# ESP32.net
KiCad netlist of a schematic drawn in Altium Designer
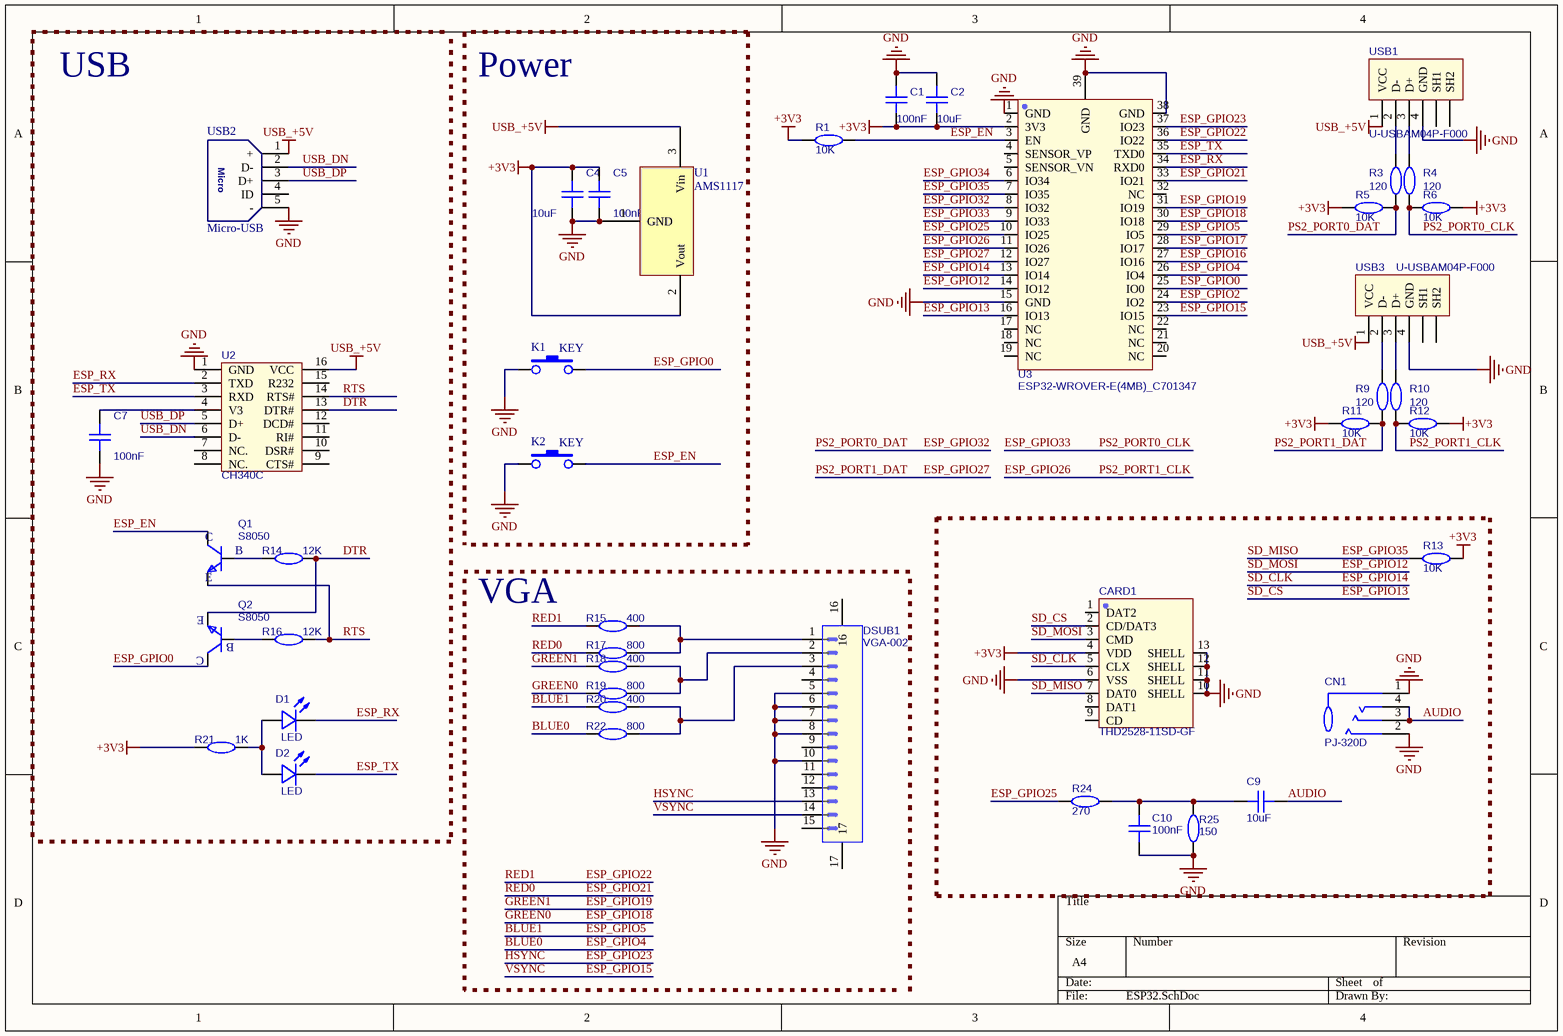
[diagram p0: ESP32.SchDoc]

(export (version "E")
  (design (tool "Eeschema 10.0.6"))
  (components
    (comp (ref "C1")
      (value "100nF")
      (footprint "0805C")
      (fields
        (field (name "BOM_SUPPLIER PART") "C325469")
        (field (name "BOM_MANUFACTURER PART") "CC0603GRNPO9BN200")
        (field (name "CONTRIBUTOR") "LCSC")
      )
      (libsource (lib "miscpcb") (part "CAP_0603"))
    )
    (comp (ref "C2")
      (value "10uF")
      (footprint "0805C")
      (fields
        (field (name "BOM_SUPPLIER PART") "C325469")
        (field (name "BOM_MANUFACTURER PART") "CC0603GRNPO9BN200")
        (field (name "CONTRIBUTOR") "LCSC")
      )
      (libsource (lib "miscpcb") (part "CAP_0603"))
    )
    (comp (ref "C4")
      (value "10uF")
      (footprint "0805C")
      (fields
        (field (name "BOM_SUPPLIER PART") "C325469")
        (field (name "BOM_MANUFACTURER PART") "CC0603GRNPO9BN200")
        (field (name "CONTRIBUTOR") "LCSC")
      )
      (libsource (lib "miscpcb") (part "CAP_0603"))
    )
    (comp (ref "C5")
      (value "100nF")
      (footprint "0805C")
      (fields
        (field (name "BOM_SUPPLIER PART") "C325469")
        (field (name "BOM_MANUFACTURER PART") "CC0603GRNPO9BN200")
        (field (name "CONTRIBUTOR") "LCSC")
      )
      (libsource (lib "miscpcb") (part "CAP_0603"))
    )
    (comp (ref "C7")
      (value "100nF")
      (footprint "0805C")
      (fields
        (field (name "BOM_SUPPLIER PART") "C325469")
        (field (name "BOM_MANUFACTURER PART") "CC0603GRNPO9BN200")
        (field (name "CONTRIBUTOR") "LCSC")
      )
      (libsource (lib "miscpcb") (part "CAP_0603"))
    )
    (comp (ref "C9")
      (value "10uF")
      (footprint "0805C")
      (fields
        (field (name "BOM_SUPPLIER PART") "C325469")
        (field (name "BOM_MANUFACTURER PART") "CC0603GRNPO9BN200")
        (field (name "CONTRIBUTOR") "LCSC")
      )
      (libsource (lib "miscpcb") (part "CAP_0603"))
    )
    (comp (ref "C10")
      (value "100nF")
      (footprint "0805C")
      (fields
        (field (name "BOM_SUPPLIER PART") "C325469")
        (field (name "BOM_MANUFACTURER PART") "CC0603GRNPO9BN200")
        (field (name "CONTRIBUTOR") "LCSC")
      )
      (libsource (lib "miscpcb") (part "CAP_0603"))
    )
    (comp (ref "CARD1")
      (value "THD2528-11SD-GF")
      (footprint "Micro SD")
      (fields (field (name "BOM_SUPPLIER PART") "C283232") (field (name "CONTRIBUTOR") "LCSC"))
      (libsource (lib "esp32") (part "THD2528-11SD-GF"))
    )
    (comp (ref "CN1")
      (value "PJ-320D")
      (footprint "AUDIO-SMD_PJ-320D")
      (fields (field (name "BOM_SUPPLIER PART") "C431535") (field (name "CONTRIBUTOR") "LCSC"))
      (libsource (lib "esp32") (part "PJ-320D"))
    )
    (comp (ref "D1")
      (value "LED")
      (footprint "LED-0603")
      (fields (field (name "BOM_MANUFACTURER PART") "?"))
      (libsource (lib "miscpcb") (part "LED-Y"))
    )
    (comp (ref "D2")
      (value "LED")
      (footprint "LED-0603")
      (fields (field (name "BOM_MANUFACTURER PART") "?"))
      (libsource (lib "miscpcb") (part "LED-Y"))
    )
    (comp (ref "DSUB1")
      (value "VGA-002")
      (footprint "VGA15/F/90")
      (fields (field (name "BOM_SUPPLIER PART") "C138387"))
      (libsource (lib "esp32") (part "VGA-002"))
    )
    (comp (ref "K1")
      (value "KEY")
      (footprint "SW-SMD_L3.9-W2.9-P4.15-LS5.0")
      (libsource (lib "开关-轻触开关") (part "KEY"))
    )
    (comp (ref "K2")
      (value "KEY")
      (footprint "SW-SMD_L3.9-W2.9-P4.15-LS5.0")
      (libsource (lib "开关-轻触开关") (part "KEY"))
    )
    (comp (ref "Q1")
      (value "S8050")
      (footprint "SOT-23_L2.9-W1.3-P0.95-LS2.4-BR")
      (fields (field (name "BOM_SUPPLIER PART") "C414195") (field (name "CONTRIBUTOR") "LCSC"))
      (libsource (lib "miscpcb") (part "S8050"))
    )
    (comp (ref "Q2")
      (value "S8050")
      (footprint "SOT-23_L2.9-W1.3-P0.95-LS2.4-BR")
      (fields (field (name "BOM_SUPPLIER PART") "C414195") (field (name "CONTRIBUTOR") "LCSC"))
      (libsource (lib "miscpcb") (part "S8050"))
    )
    (comp (ref "R1")
      (value "10K")
      (footprint "0805R")
      (fields
        (field (name "BOM_MANUFACTURER PART") "CR0603JA0301G")
        (field (name "BOM_SUPPLIER PART") "C101323")
      )
      (libsource (lib "miscpcb") (part "RES_0603"))
    )
    (comp (ref "R3")
      (value "120")
      (footprint "0805R")
      (fields
        (field (name "BOM_MANUFACTURER PART") "CR0603JA0301G")
        (field (name "BOM_SUPPLIER PART") "C101323")
      )
      (libsource (lib "miscpcb") (part "RES_0603"))
    )
    (comp (ref "R4")
      (value "120")
      (footprint "0805R")
      (fields
        (field (name "BOM_MANUFACTURER PART") "CR0603JA0301G")
        (field (name "BOM_SUPPLIER PART") "C101323")
      )
      (libsource (lib "miscpcb") (part "RES_0603"))
    )
    (comp (ref "R5")
      (value "10K")
      (footprint "0805R")
      (fields
        (field (name "BOM_MANUFACTURER PART") "CR0603JA0301G")
        (field (name "BOM_SUPPLIER PART") "C101323")
      )
      (libsource (lib "miscpcb") (part "RES_0603"))
    )
    (comp (ref "R6")
      (value "10K")
      (footprint "0805R")
      (fields
        (field (name "BOM_MANUFACTURER PART") "CR0603JA0301G")
        (field (name "BOM_SUPPLIER PART") "C101323")
      )
      (libsource (lib "miscpcb") (part "RES_0603"))
    )
    (comp (ref "R9")
      (value "120")
      (footprint "0805R")
      (fields
        (field (name "BOM_MANUFACTURER PART") "CR0603JA0301G")
        (field (name "BOM_SUPPLIER PART") "C101323")
      )
      (libsource (lib "miscpcb") (part "RES_0603"))
    )
    (comp (ref "R10")
      (value "120")
      (footprint "0805R")
      (fields
        (field (name "BOM_MANUFACTURER PART") "CR0603JA0301G")
        (field (name "BOM_SUPPLIER PART") "C101323")
      )
      (libsource (lib "miscpcb") (part "RES_0603"))
    )
    (comp (ref "R11")
      (value "10K")
      (footprint "0805R")
      (fields
        (field (name "BOM_MANUFACTURER PART") "CR0603JA0301G")
        (field (name "BOM_SUPPLIER PART") "C101323")
      )
      (libsource (lib "miscpcb") (part "RES_0603"))
    )
    (comp (ref "R12")
      (value "10K")
      (footprint "0805R")
      (fields
        (field (name "BOM_MANUFACTURER PART") "CR0603JA0301G")
        (field (name "BOM_SUPPLIER PART") "C101323")
      )
      (libsource (lib "miscpcb") (part "RES_0603"))
    )
    (comp (ref "R13")
      (value "10K")
      (footprint "0805R")
      (fields
        (field (name "BOM_MANUFACTURER PART") "CR0603JA0301G")
        (field (name "BOM_SUPPLIER PART") "C101323")
      )
      (libsource (lib "miscpcb") (part "RES_0603"))
    )
    (comp (ref "R14")
      (value "12K")
      (footprint "0805R")
      (fields
        (field (name "BOM_MANUFACTURER PART") "CR0603JA0301G")
        (field (name "BOM_SUPPLIER PART") "C101323")
      )
      (libsource (lib "miscpcb") (part "RES_0603"))
    )
    (comp (ref "R15")
      (value "400")
      (footprint "0805R")
      (fields
        (field (name "BOM_MANUFACTURER PART") "CR0603JA0301G")
        (field (name "BOM_SUPPLIER PART") "C101323")
      )
      (libsource (lib "miscpcb") (part "RES_0603"))
    )
    (comp (ref "R16")
      (value "12K")
      (footprint "0805R")
      (fields
        (field (name "BOM_MANUFACTURER PART") "CR0603JA0301G")
        (field (name "BOM_SUPPLIER PART") "C101323")
      )
      (libsource (lib "miscpcb") (part "RES_0603"))
    )
    (comp (ref "R17")
      (value "800")
      (footprint "0805R")
      (fields
        (field (name "BOM_MANUFACTURER PART") "CR0603JA0301G")
        (field (name "BOM_SUPPLIER PART") "C101323")
      )
      (libsource (lib "miscpcb") (part "RES_0603"))
    )
    (comp (ref "R18")
      (value "400")
      (footprint "0805R")
      (fields
        (field (name "BOM_MANUFACTURER PART") "CR0603JA0301G")
        (field (name "BOM_SUPPLIER PART") "C101323")
      )
      (libsource (lib "miscpcb") (part "RES_0603"))
    )
    (comp (ref "R19")
      (value "800")
      (footprint "0805R")
      (fields
        (field (name "BOM_MANUFACTURER PART") "CR0603JA0301G")
        (field (name "BOM_SUPPLIER PART") "C101323")
      )
      (libsource (lib "miscpcb") (part "RES_0603"))
    )
    (comp (ref "R20")
      (value "400")
      (footprint "0805R")
      (fields
        (field (name "BOM_MANUFACTURER PART") "CR0603JA0301G")
        (field (name "BOM_SUPPLIER PART") "C101323")
      )
      (libsource (lib "miscpcb") (part "RES_0603"))
    )
    (comp (ref "R21")
      (value "1K")
      (footprint "0805R")
      (fields
        (field (name "BOM_MANUFACTURER PART") "CR0603JA0301G")
        (field (name "BOM_SUPPLIER PART") "C101323")
      )
      (libsource (lib "miscpcb") (part "RES_0603"))
    )
    (comp (ref "R22")
      (value "800")
      (footprint "0805R")
      (fields
        (field (name "BOM_MANUFACTURER PART") "CR0603JA0301G")
        (field (name "BOM_SUPPLIER PART") "C101323")
      )
      (libsource (lib "miscpcb") (part "RES_0603"))
    )
    (comp (ref "R24")
      (value "270")
      (footprint "0805R")
      (fields
        (field (name "BOM_MANUFACTURER PART") "CR0603JA0301G")
        (field (name "BOM_SUPPLIER PART") "C101323")
      )
      (libsource (lib "miscpcb") (part "RES_0603"))
    )
    (comp (ref "R25")
      (value "150")
      (footprint "0805R")
      (fields
        (field (name "BOM_MANUFACTURER PART") "CR0603JA0301G")
        (field (name "BOM_SUPPLIER PART") "C101323")
      )
      (libsource (lib "miscpcb") (part "RES_0603"))
    )
    (comp (ref "U1")
      (value "AMS1117")
      (footprint "SOT223")
      (description "三端稳压芯片")
      (libsource (lib "芯片-电源芯片") (part "AMS1117"))
    )
    (comp (ref "U2")
      (value "CH340C")
      (footprint "SOP16")
      (fields (field (name "BOM_SUPPLIER PART") "C84681"))
      (libsource (lib "esp32") (part "CH340C"))
    )
    (comp (ref "U3")
      (value "ESP32-WROVER-E(4MB)_C701347")
      (footprint "XCVR_ESP32-WROVER-I")
      (fields
        (field (name "BOM_SUPPLIER PART") "C701347")
        (field (name "BOM_MANUFACTURER PART") "ESP32-WROVER-E(4MB)")
        (field (name "CONTRIBUTOR") "LCSC")
      )
      (libsource (lib "esp32") (part "ESP32-WROVER-E(4MB)_C701347"))
    )
    (comp (ref "USB1")
      (value "U-USBAM04P-F000")
      (footprint "USB-A/S_B")
      (fields (field (name "BOM_SUPPLIER PART") "C386738") (field (name "CONTRIBUTOR") "LCSC"))
      (libsource (lib "esp32") (part "U-USBAM04P-F000"))
    )
    (comp (ref "USB2")
      (value "Micro-USB")
      (footprint "USB-MICRO_A")
      (libsource (lib "插座-USB连接器") (part "Micro-USB"))
    )
    (comp (ref "USB3")
      (value "U-USBAM04P-F000")
      (footprint "USB-A/S_B")
      (fields (field (name "BOM_SUPPLIER PART") "C386738") (field (name "CONTRIBUTOR") "LCSC"))
      (libsource (lib "esp32") (part "U-USBAM04P-F000"))
    )
  )
  (nets
    (net (code "1") (name "+3V3") (class "Default")
      (node (ref "C1") (pin "2") (pinfunction "2_2") (pintype "passive"))
      (node (ref "C2") (pin "2") (pinfunction "2_2") (pintype "passive"))
      (node (ref "C4") (pin "2") (pinfunction "2_2") (pintype "passive"))
      (node (ref "C5") (pin "2") (pinfunction "2_2") (pintype "passive"))
      (node (ref "CARD1") (pin "4") (pinfunction "VDD_4") (pintype "passive"))
      (node (ref "R1") (pin "1") (pinfunction "1_1") (pintype "passive"))
      (node (ref "R11") (pin "2") (pinfunction "2_2") (pintype "passive"))
      (node (ref "R12") (pin "1") (pinfunction "1_1") (pintype "passive"))
      (node (ref "R13") (pin "1") (pinfunction "1_1") (pintype "passive"))
      (node (ref "R21") (pin "2") (pinfunction "2_2") (pintype "passive"))
      (node (ref "R5") (pin "2") (pinfunction "2_2") (pintype "passive"))
      (node (ref "R6") (pin "1") (pinfunction "1_1") (pintype "passive"))
      (node (ref "U1") (pin "2") (pinfunction "Vout_2") (pintype "passive"))
      (node (ref "U3") (pin "2") (pinfunction "3V3_2") (pintype "passive"))
    )
    (net (code "2") (name "/AUDIO") (class "Default")
      (node (ref "C9") (pin "1") (pinfunction "1_1") (pintype "passive"))
      (node (ref "CN1") (pin "3") (pinfunction "3_3") (pintype "passive"))
      (node (ref "CN1") (pin "4") (pinfunction "4_4") (pintype "passive"))
    )
    (net (code "3") (name "/BLUE0") (class "Default")
      (node (ref "R22") (pin "2") (pinfunction "2_2") (pintype "passive"))
      (node (ref "U3") (pin "26") (pinfunction "IO4_26") (pintype "passive"))
    )
    (net (code "4") (name "/BLUE1") (class "Default")
      (node (ref "R20") (pin "2") (pinfunction "2_2") (pintype "passive"))
      (node (ref "U3") (pin "29") (pinfunction "IO5_29") (pintype "passive"))
    )
    (net (code "5") (name "/DTR") (class "Default")
      (node (ref "Q2") (pin "2") (pinfunction "E_2") (pintype "passive"))
      (node (ref "R14") (pin "1") (pinfunction "1_1") (pintype "passive"))
      (node (ref "U2") (pin "13") (pinfunction "DTR#_13") (pintype "passive"))
    )
    (net (code "6") (name "/ESP_EN") (class "Default")
      (node (ref "K2") (pin "3") (pinfunction "3_3") (pintype "passive"))
      (node (ref "Q1") (pin "3") (pinfunction "C_3") (pintype "passive"))
      (node (ref "R1") (pin "2") (pinfunction "2_2") (pintype "passive"))
      (node (ref "U3") (pin "3") (pinfunction "EN_3") (pintype "passive"))
    )
    (net (code "7") (name "/ESP_GPIO0") (class "Default")
      (node (ref "K1") (pin "3") (pinfunction "3_3") (pintype "passive"))
      (node (ref "Q2") (pin "3") (pinfunction "C_3") (pintype "passive"))
      (node (ref "U3") (pin "25") (pinfunction "IO0_25") (pintype "passive"))
    )
    (net (code "8") (name "/ESP_GPIO2") (class "Default")
      (node (ref "U3") (pin "24") (pinfunction "IO2_24") (pintype "passive"))
    )
    (net (code "9") (name "/ESP_GPIO12") (class "Default")
      (node (ref "CARD1") (pin "3") (pinfunction "CMD_3") (pintype "passive"))
      (node (ref "U3") (pin "14") (pinfunction "IO12_14") (pintype "passive"))
    )
    (net (code "10") (name "/ESP_GPIO13") (class "Default")
      (node (ref "CARD1") (pin "2") (pinfunction "CD/DAT3_2") (pintype "passive"))
      (node (ref "U3") (pin "16") (pinfunction "IO13_16") (pintype "passive"))
    )
    (net (code "11") (name "/ESP_GPIO14") (class "Default")
      (node (ref "CARD1") (pin "5") (pinfunction "CLX_5") (pintype "passive"))
      (node (ref "U3") (pin "13") (pinfunction "IO14_13") (pintype "passive"))
    )
    (net (code "12") (name "/ESP_GPIO15") (class "Default")
      (node (ref "DSUB1") (pin "14") (pinfunction "14_14") (pintype "passive"))
      (node (ref "U3") (pin "23") (pinfunction "IO15_23") (pintype "passive"))
    )
    (net (code "13") (name "/ESP_GPIO16") (class "Default")
      (node (ref "U3") (pin "27") (pinfunction "IO16_27") (pintype "passive"))
    )
    (net (code "14") (name "/ESP_GPIO17") (class "Default")
      (node (ref "U3") (pin "28") (pinfunction "IO17_28") (pintype "passive"))
    )
    (net (code "15") (name "/ESP_GPIO18") (class "Default")
      (node (ref "R19") (pin "2") (pinfunction "2_2") (pintype "passive"))
      (node (ref "U3") (pin "30") (pinfunction "IO18_30") (pintype "passive"))
    )
    (net (code "16") (name "/ESP_GPIO19") (class "Default")
      (node (ref "R18") (pin "2") (pinfunction "2_2") (pintype "passive"))
      (node (ref "U3") (pin "31") (pinfunction "IO19_31") (pintype "passive"))
    )
    (net (code "17") (name "/ESP_GPIO21") (class "Default")
      (node (ref "R17") (pin "2") (pinfunction "2_2") (pintype "passive"))
      (node (ref "U3") (pin "33") (pinfunction "IO21_33") (pintype "passive"))
    )
    (net (code "18") (name "/ESP_GPIO22") (class "Default")
      (node (ref "R15") (pin "2") (pinfunction "2_2") (pintype "passive"))
      (node (ref "U3") (pin "36") (pinfunction "IO22_36") (pintype "passive"))
    )
    (net (code "19") (name "/ESP_GPIO23") (class "Default")
      (node (ref "DSUB1") (pin "13") (pinfunction "13_13") (pintype "passive"))
      (node (ref "U3") (pin "37") (pinfunction "IO23_37") (pintype "passive"))
    )
    (net (code "20") (name "/ESP_GPIO25") (class "Default")
      (node (ref "R24") (pin "2") (pinfunction "2_2") (pintype "passive"))
      (node (ref "U3") (pin "10") (pinfunction "IO25_10") (pintype "passive"))
    )
    (net (code "21") (name "/ESP_GPIO26") (class "Default")
      (node (ref "R10") (pin "2") (pinfunction "2_2") (pintype "passive"))
      (node (ref "R12") (pin "2") (pinfunction "2_2") (pintype "passive"))
      (node (ref "U3") (pin "11") (pinfunction "IO26_11") (pintype "passive"))
    )
    (net (code "22") (name "/ESP_GPIO27") (class "Default")
      (node (ref "R11") (pin "1") (pinfunction "1_1") (pintype "passive"))
      (node (ref "R9") (pin "2") (pinfunction "2_2") (pintype "passive"))
      (node (ref "U3") (pin "12") (pinfunction "IO27_12") (pintype "passive"))
    )
    (net (code "23") (name "/ESP_GPIO32") (class "Default")
      (node (ref "R3") (pin "2") (pinfunction "2_2") (pintype "passive"))
      (node (ref "R5") (pin "1") (pinfunction "1_1") (pintype "passive"))
      (node (ref "U3") (pin "8") (pinfunction "IO32_8") (pintype "passive"))
    )
    (net (code "24") (name "/ESP_GPIO33") (class "Default")
      (node (ref "R4") (pin "2") (pinfunction "2_2") (pintype "passive"))
      (node (ref "R6") (pin "2") (pinfunction "2_2") (pintype "passive"))
      (node (ref "U3") (pin "9") (pinfunction "IO33_9") (pintype "passive"))
    )
    (net (code "25") (name "/ESP_GPIO34") (class "Default")
      (node (ref "U3") (pin "6") (pinfunction "IO34_6") (pintype "passive"))
    )
    (net (code "26") (name "/ESP_GPIO35") (class "Default")
      (node (ref "CARD1") (pin "7") (pinfunction "DAT0_7") (pintype "passive"))
      (node (ref "R13") (pin "2") (pinfunction "2_2") (pintype "passive"))
      (node (ref "U3") (pin "7") (pinfunction "IO35_7") (pintype "passive"))
    )
    (net (code "27") (name "/ESP_RX") (class "Default")
      (node (ref "D1") (pin "2") (pinfunction "K_2") (pintype "passive"))
      (node (ref "U2") (pin "2") (pinfunction "TXD_2") (pintype "passive"))
      (node (ref "U3") (pin "34") (pinfunction "RXD0_34") (pintype "passive"))
    )
    (net (code "28") (name "/ESP_TX") (class "Default")
      (node (ref "D2") (pin "2") (pinfunction "K_2") (pintype "passive"))
      (node (ref "U2") (pin "3") (pinfunction "RXD_3") (pintype "passive"))
      (node (ref "U3") (pin "35") (pinfunction "TXD0_35") (pintype "passive"))
    )
    (net (code "29") (name "/RTS") (class "Default")
      (node (ref "Q1") (pin "2") (pinfunction "E_2") (pintype "passive"))
      (node (ref "R16") (pin "1") (pinfunction "1_1") (pintype "passive"))
      (node (ref "U2") (pin "14") (pinfunction "RTS#_14") (pintype "passive"))
    )
    (net (code "30") (name "/USB_DN") (class "Default")
      (node (ref "U2") (pin "6") (pinfunction "D-_6") (pintype "passive"))
      (node (ref "USB2") (pin "2") (pinfunction "D-_2") (pintype "passive"))
    )
    (net (code "31") (name "/USB_DP") (class "Default")
      (node (ref "U2") (pin "5") (pinfunction "D+_5") (pintype "passive"))
      (node (ref "USB2") (pin "3") (pinfunction "D+_3") (pintype "passive"))
    )
    (net (code "32") (name "GND") (class "Default")
      (node (ref "C1") (pin "1") (pinfunction "1_1") (pintype "passive"))
      (node (ref "C10") (pin "1") (pinfunction "1_1") (pintype "passive"))
      (node (ref "C2") (pin "1") (pinfunction "1_1") (pintype "passive"))
      (node (ref "C4") (pin "1") (pinfunction "1_1") (pintype "passive"))
      (node (ref "C5") (pin "1") (pinfunction "1_1") (pintype "passive"))
      (node (ref "C7") (pin "1") (pinfunction "1_1") (pintype "passive"))
      (node (ref "CARD1") (pin "10") (pinfunction "SHELL_10") (pintype "passive"))
      (node (ref "CARD1") (pin "11") (pinfunction "SHELL_11") (pintype "passive"))
      (node (ref "CARD1") (pin "12") (pinfunction "SHELL_12") (pintype "passive"))
      (node (ref "CARD1") (pin "13") (pinfunction "SHELL_13") (pintype "passive"))
      (node (ref "CARD1") (pin "6") (pinfunction "VSS_6") (pintype "passive"))
      (node (ref "CN1") (pin "1") (pinfunction "1_1") (pintype "passive"))
      (node (ref "CN1") (pin "2") (pinfunction "2_2") (pintype "passive"))
      (node (ref "DSUB1") (pin "10") (pinfunction "10_10") (pintype "passive"))
      (node (ref "DSUB1") (pin "5") (pinfunction "5_5") (pintype "passive"))
      (node (ref "DSUB1") (pin "6") (pinfunction "6_6") (pintype "passive"))
      (node (ref "DSUB1") (pin "7") (pinfunction "7_7") (pintype "passive"))
      (node (ref "DSUB1") (pin "8") (pinfunction "8_8") (pintype "passive"))
      (node (ref "K1") (pin "1") (pinfunction "1_1") (pintype "passive"))
      (node (ref "K2") (pin "1") (pinfunction "1_1") (pintype "passive"))
      (node (ref "R25") (pin "2") (pinfunction "2_2") (pintype "passive"))
      (node (ref "U1") (pin "1") (pinfunction "GND_1") (pintype "passive"))
      (node (ref "U2") (pin "1") (pinfunction "GND_1") (pintype "passive"))
      (node (ref "U3") (pin "1") (pinfunction "GND_1") (pintype "passive"))
      (node (ref "U3") (pin "15") (pinfunction "GND_15") (pintype "passive"))
      (node (ref "U3") (pin "38") (pinfunction "GND_38") (pintype "passive"))
      (node (ref "U3") (pin "39") (pinfunction "GND_39") (pintype "passive"))
      (node (ref "USB1") (pin "4") (pinfunction "GND_4") (pintype "passive"))
      (node (ref "USB2") (pin "5") (pinfunction "-_5") (pintype "passive"))
      (node (ref "USB3") (pin "4") (pinfunction "GND_4") (pintype "passive"))
    )
    (net (code "33") (name "Net-(C10-Pad2)") (class "Default")
      (node (ref "C10") (pin "2") (pinfunction "2_2") (pintype "passive"))
      (node (ref "C9") (pin "2") (pinfunction "2_2") (pintype "passive"))
      (node (ref "R24") (pin "1") (pinfunction "1_1") (pintype "passive"))
      (node (ref "R25") (pin "1") (pinfunction "1_1") (pintype "passive"))
    )
    (net (code "34") (name "Net-(D1-A)") (class "Default")
      (node (ref "D1") (pin "1") (pinfunction "A_1") (pintype "passive"))
      (node (ref "D2") (pin "1") (pinfunction "A_1") (pintype "passive"))
      (node (ref "R21") (pin "1") (pinfunction "1_1") (pintype "passive"))
    )
    (net (code "35") (name "Net-(DSUB1-Pad1)") (class "Default")
      (node (ref "DSUB1") (pin "1") (pinfunction "1_1") (pintype "passive"))
      (node (ref "R15") (pin "1") (pinfunction "1_1") (pintype "passive"))
      (node (ref "R17") (pin "1") (pinfunction "1_1") (pintype "passive"))
    )
    (net (code "36") (name "Net-(DSUB1-Pad2)") (class "Default")
      (node (ref "DSUB1") (pin "2") (pinfunction "2_2") (pintype "passive"))
      (node (ref "R18") (pin "1") (pinfunction "1_1") (pintype "passive"))
      (node (ref "R19") (pin "1") (pinfunction "1_1") (pintype "passive"))
    )
    (net (code "37") (name "Net-(DSUB1-Pad3)") (class "Default")
      (node (ref "DSUB1") (pin "3") (pinfunction "3_3") (pintype "passive"))
      (node (ref "R20") (pin "1") (pinfunction "1_1") (pintype "passive"))
      (node (ref "R22") (pin "1") (pinfunction "1_1") (pintype "passive"))
    )
    (net (code "38") (name "Net-(Q1-B)") (class "Default")
      (node (ref "Q1") (pin "1") (pinfunction "B_1") (pintype "passive"))
      (node (ref "R14") (pin "2") (pinfunction "2_2") (pintype "passive"))
    )
    (net (code "39") (name "Net-(Q2-B)") (class "Default")
      (node (ref "Q2") (pin "1") (pinfunction "B_1") (pintype "passive"))
      (node (ref "R16") (pin "2") (pinfunction "2_2") (pintype "passive"))
    )
    (net (code "40") (name "Net-(U2-V3)") (class "Default")
      (node (ref "C7") (pin "2") (pinfunction "2_2") (pintype "passive"))
      (node (ref "U2") (pin "4") (pinfunction "V3_4") (pintype "passive"))
    )
    (net (code "41") (name "Net-(USB1-D+)") (class "Default")
      (node (ref "R4") (pin "1") (pinfunction "1_1") (pintype "passive"))
      (node (ref "USB1") (pin "3") (pinfunction "D+_3") (pintype "passive"))
    )
    (net (code "42") (name "Net-(USB1-D-)") (class "Default")
      (node (ref "R3") (pin "1") (pinfunction "1_1") (pintype "passive"))
      (node (ref "USB1") (pin "2") (pinfunction "D-_2") (pintype "passive"))
    )
    (net (code "43") (name "Net-(USB3-D+)") (class "Default")
      (node (ref "R10") (pin "1") (pinfunction "1_1") (pintype "passive"))
      (node (ref "USB3") (pin "3") (pinfunction "D+_3") (pintype "passive"))
    )
    (net (code "44") (name "Net-(USB3-D-)") (class "Default")
      (node (ref "R9") (pin "1") (pinfunction "1_1") (pintype "passive"))
      (node (ref "USB3") (pin "2") (pinfunction "D-_2") (pintype "passive"))
    )
    (net (code "45") (name "USB_+5V") (class "Default")
      (node (ref "U1") (pin "3") (pinfunction "Vin_3") (pintype "passive"))
      (node (ref "U2") (pin "16") (pinfunction "VCC_16") (pintype "passive"))
      (node (ref "USB1") (pin "1") (pinfunction "VCC_1") (pintype "passive"))
      (node (ref "USB2") (pin "1") (pinfunction "+_1") (pintype "passive"))
      (node (ref "USB3") (pin "1") (pinfunction "VCC_1") (pintype "passive"))
    )
    (net (code "46") (name "unconnected-(CARD1-CD-Pad9)") (class "Default")
      (node (ref "CARD1") (pin "9") (pinfunction "CD_9") (pintype "passive"))
    )
    (net (code "47") (name "unconnected-(CARD1-DAT1-Pad8)") (class "Default")
      (node (ref "CARD1") (pin "8") (pinfunction "DAT1_8") (pintype "passive"))
    )
    (net (code "48") (name "unconnected-(CARD1-DAT2-Pad1)") (class "Default")
      (node (ref "CARD1") (pin "1") (pinfunction "DAT2_1") (pintype "passive"))
    )
    (net (code "49") (name "unconnected-(DSUB1-Pad4)") (class "Default")
      (node (ref "DSUB1") (pin "4") (pinfunction "4_4") (pintype "passive"))
    )
    (net (code "50") (name "unconnected-(DSUB1-Pad9)") (class "Default")
      (node (ref "DSUB1") (pin "9") (pinfunction "9_9") (pintype "passive"))
    )
    (net (code "51") (name "unconnected-(DSUB1-Pad11)") (class "Default")
      (node (ref "DSUB1") (pin "11") (pinfunction "11_11") (pintype "passive"))
    )
    (net (code "52") (name "unconnected-(DSUB1-Pad12)") (class "Default")
      (node (ref "DSUB1") (pin "12") (pinfunction "12_12") (pintype "passive"))
    )
    (net (code "53") (name "unconnected-(DSUB1-Pad15)") (class "Default")
      (node (ref "DSUB1") (pin "15") (pinfunction "15_15") (pintype "passive"))
    )
    (net (code "54") (name "unconnected-(DSUB1-Pad16)") (class "Default")
      (node (ref "DSUB1") (pin "16") (pinfunction "16_16") (pintype "passive"))
    )
    (net (code "55") (name "unconnected-(DSUB1-Pad17)") (class "Default")
      (node (ref "DSUB1") (pin "17") (pinfunction "17_17") (pintype "passive"))
    )
    (net (code "56") (name "unconnected-(U2-CTS#-Pad9)") (class "Default")
      (node (ref "U2") (pin "9") (pinfunction "CTS#_9") (pintype "passive"))
    )
    (net (code "57") (name "unconnected-(U2-DCD#-Pad12)") (class "Default")
      (node (ref "U2") (pin "12") (pinfunction "DCD#_12") (pintype "passive"))
    )
    (net (code "58") (name "unconnected-(U2-DSR#-Pad10)") (class "Default")
      (node (ref "U2") (pin "10") (pinfunction "DSR#_10") (pintype "passive"))
    )
    (net (code "59") (name "unconnected-(U2-NC.-Pad7)") (class "Default")
      (node (ref "U2") (pin "7") (pinfunction "NC._7") (pintype "passive"))
    )
    (net (code "60") (name "unconnected-(U2-NC.-Pad8)") (class "Default")
      (node (ref "U2") (pin "8") (pinfunction "NC._8") (pintype "passive"))
    )
    (net (code "61") (name "unconnected-(U2-R232-Pad15)") (class "Default")
      (node (ref "U2") (pin "15") (pinfunction "R232_15") (pintype "passive"))
    )
    (net (code "62") (name "unconnected-(U2-RI#-Pad11)") (class "Default")
      (node (ref "U2") (pin "11") (pinfunction "RI#_11") (pintype "passive"))
    )
    (net (code "63") (name "unconnected-(U3-NC-Pad17)") (class "Default")
      (node (ref "U3") (pin "17") (pinfunction "NC_17") (pintype "passive"))
    )
    (net (code "64") (name "unconnected-(U3-NC-Pad18)") (class "Default")
      (node (ref "U3") (pin "18") (pinfunction "NC_18") (pintype "passive"))
    )
    (net (code "65") (name "unconnected-(U3-NC-Pad19)") (class "Default")
      (node (ref "U3") (pin "19") (pinfunction "NC_19") (pintype "passive"))
    )
    (net (code "66") (name "unconnected-(U3-NC-Pad20)") (class "Default")
      (node (ref "U3") (pin "20") (pinfunction "NC_20") (pintype "passive"))
    )
    (net (code "67") (name "unconnected-(U3-NC-Pad21)") (class "Default")
      (node (ref "U3") (pin "21") (pinfunction "NC_21") (pintype "passive"))
    )
    (net (code "68") (name "unconnected-(U3-NC-Pad22)") (class "Default")
      (node (ref "U3") (pin "22") (pinfunction "NC_22") (pintype "passive"))
    )
    (net (code "69") (name "unconnected-(U3-NC-Pad32)") (class "Default")
      (node (ref "U3") (pin "32") (pinfunction "NC_32") (pintype "passive"))
    )
    (net (code "70") (name "unconnected-(U3-SENSOR_VN-Pad5)") (class "Default")
      (node (ref "U3") (pin "5") (pinfunction "SENSOR_VN_5") (pintype "passive"))
    )
    (net (code "71") (name "unconnected-(U3-SENSOR_VP-Pad4)") (class "Default")
      (node (ref "U3") (pin "4") (pinfunction "SENSOR_VP_4") (pintype "passive"))
    )
    (net (code "72") (name "unconnected-(USB1-PadSH1)") (class "Default")
      (node (ref "USB1") (pin "SH1") (pinfunction "SH1_SH1") (pintype "passive"))
    )
    (net (code "73") (name "unconnected-(USB1-PadSH2)") (class "Default")
      (node (ref "USB1") (pin "SH2") (pinfunction "SH2_SH2") (pintype "passive"))
    )
    (net (code "74") (name "unconnected-(USB2-ID-Pad4)") (class "Default")
      (node (ref "USB2") (pin "4") (pinfunction "ID_4") (pintype "passive"))
    )
    (net (code "75") (name "unconnected-(USB3-PadSH1)") (class "Default")
      (node (ref "USB3") (pin "SH1") (pinfunction "SH1_SH1") (pintype "passive"))
    )
    (net (code "76") (name "unconnected-(USB3-PadSH2)") (class "Default")
      (node (ref "USB3") (pin "SH2") (pinfunction "SH2_SH2") (pintype "passive"))
    )
  )
)
